# DendroSchem.net
KiCad netlist of a schematic drawn in EAGLE
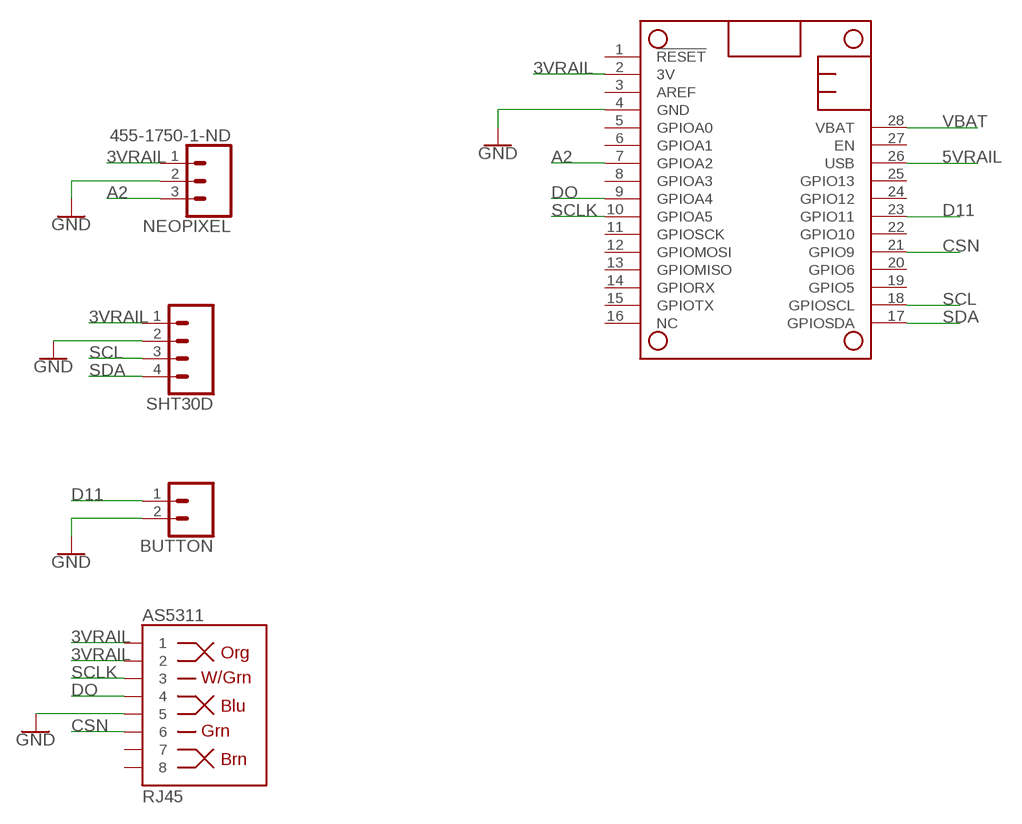
[diagram p0: schematic, sheet 1]

(export (version "E")
  (design (tool "Eeschema 10.0.6"))
  (components
    (comp (ref "AS5311")
      (value "RJ45")
      (footprint "eagle-import:RJ45-8")
      (libsource (lib "eagle-import") (part "RJ45-8"))
    )
    (comp (ref "BUTTON")
      (value "CONN_02")
      (footprint "eagle-import:1X02")
      (libsource (lib "eagle-import") (part "CONN_02"))
    )
    (comp (ref "MS1")
      (value "FEATHERWING")
      (footprint "eagle-import:FEATHERWING")
      (libsource (lib "eagle-import") (part "FEATHERWING"))
    )
    (comp (ref "NEOPIXEL")
      (value "455-1750-1-ND")
      (footprint "eagle-import:1X03")
      (libsource (lib "eagle-import") (part "CONN_03"))
    )
    (comp (ref "SHT30D")
      (value "CONN_04")
      (footprint "eagle-import:1X04")
      (libsource (lib "eagle-import") (part "CONN_04"))
    )
  )
  (nets
    (net (code "1") (name "/3VRAIL") (class "Default")
      (node (ref "AS5311") (pin "1") (pinfunction "1_1") (pintype "bidirectional"))
      (node (ref "AS5311") (pin "2") (pinfunction "2_2") (pintype "bidirectional"))
      (node (ref "MS1") (pin "2") (pinfunction "3V_2") (pintype "power_in"))
      (node (ref "NEOPIXEL") (pin "1") (pinfunction "1_1") (pintype "passive"))
      (node (ref "SHT30D") (pin "1") (pinfunction "1_1") (pintype "passive"))
    )
    (net (code "2") (name "/5VRAIL") (class "Default")
      (node (ref "MS1") (pin "26") (pinfunction "USB_26") (pintype "power_in"))
    )
    (net (code "3") (name "/A2") (class "Default")
      (node (ref "MS1") (pin "7") (pinfunction "GPIOA2_7") (pintype "bidirectional"))
      (node (ref "NEOPIXEL") (pin "3") (pinfunction "3_3") (pintype "passive"))
    )
    (net (code "4") (name "/CSN") (class "Default")
      (node (ref "AS5311") (pin "6") (pinfunction "6_6") (pintype "bidirectional"))
      (node (ref "MS1") (pin "21") (pinfunction "GPIO9_21") (pintype "bidirectional"))
    )
    (net (code "5") (name "/D11") (class "Default")
      (node (ref "BUTTON") (pin "1") (pinfunction "1_1") (pintype "passive"))
      (node (ref "MS1") (pin "23") (pinfunction "GPIO11_23") (pintype "bidirectional"))
    )
    (net (code "6") (name "/DO") (class "Default")
      (node (ref "AS5311") (pin "4") (pinfunction "4_4") (pintype "bidirectional"))
      (node (ref "MS1") (pin "9") (pinfunction "GPIOA4_9") (pintype "bidirectional"))
    )
    (net (code "7") (name "/SCL") (class "Default")
      (node (ref "MS1") (pin "18") (pinfunction "GPIOSCL_18") (pintype "bidirectional"))
      (node (ref "SHT30D") (pin "3") (pinfunction "3_3") (pintype "passive"))
    )
    (net (code "8") (name "/SCLK") (class "Default")
      (node (ref "AS5311") (pin "3") (pinfunction "3_3") (pintype "bidirectional"))
      (node (ref "MS1") (pin "10") (pinfunction "GPIOA5_10") (pintype "bidirectional"))
    )
    (net (code "9") (name "/SDA") (class "Default")
      (node (ref "MS1") (pin "17") (pinfunction "GPIOSDA_17") (pintype "bidirectional"))
      (node (ref "SHT30D") (pin "4") (pinfunction "4_4") (pintype "passive"))
    )
    (net (code "10") (name "/VBAT") (class "Default")
      (node (ref "MS1") (pin "28") (pinfunction "VBAT_28") (pintype "power_in"))
    )
    (net (code "11") (name "GND") (class "Default")
      (node (ref "AS5311") (pin "5") (pinfunction "5_5") (pintype "bidirectional"))
      (node (ref "BUTTON") (pin "2") (pinfunction "2_2") (pintype "passive"))
      (node (ref "MS1") (pin "4") (pinfunction "GND_4") (pintype "power_in"))
      (node (ref "NEOPIXEL") (pin "2") (pinfunction "2_2") (pintype "passive"))
      (node (ref "SHT30D") (pin "2") (pinfunction "2_2") (pintype "passive"))
    )
    (net (code "12") (name "unconnected-(AS5311-Pad7)") (class "Default")
      (node (ref "AS5311") (pin "7") (pinfunction "7_7") (pintype "bidirectional"))
    )
    (net (code "13") (name "unconnected-(AS5311-Pad8)") (class "Default")
      (node (ref "AS5311") (pin "8") (pinfunction "8_8") (pintype "bidirectional"))
    )
    (net (code "14") (name "unconnected-(MS1-AREF-Pad3)") (class "Default")
      (node (ref "MS1") (pin "3") (pinfunction "AREF_3") (pintype "passive"))
    )
    (net (code "15") (name "unconnected-(MS1-EN-Pad27)") (class "Default")
      (node (ref "MS1") (pin "27") (pinfunction "EN_27") (pintype "passive"))
    )
    (net (code "16") (name "unconnected-(MS1-GPIO5-Pad19)") (class "Default")
      (node (ref "MS1") (pin "19") (pinfunction "GPIO5_19") (pintype "bidirectional"))
    )
    (net (code "17") (name "unconnected-(MS1-GPIO6-Pad20)") (class "Default")
      (node (ref "MS1") (pin "20") (pinfunction "GPIO6_20") (pintype "bidirectional"))
    )
    (net (code "18") (name "unconnected-(MS1-GPIO10-Pad22)") (class "Default")
      (node (ref "MS1") (pin "22") (pinfunction "GPIO10_22") (pintype "bidirectional"))
    )
    (net (code "19") (name "unconnected-(MS1-GPIO12-Pad24)") (class "Default")
      (node (ref "MS1") (pin "24") (pinfunction "GPIO12_24") (pintype "bidirectional"))
    )
    (net (code "20") (name "unconnected-(MS1-GPIO13-Pad25)") (class "Default")
      (node (ref "MS1") (pin "25") (pinfunction "GPIO13_25") (pintype "bidirectional"))
    )
    (net (code "21") (name "unconnected-(MS1-GPIOA0-Pad5)") (class "Default")
      (node (ref "MS1") (pin "5") (pinfunction "GPIOA0_5") (pintype "bidirectional"))
    )
    (net (code "22") (name "unconnected-(MS1-GPIOA1-Pad6)") (class "Default")
      (node (ref "MS1") (pin "6") (pinfunction "GPIOA1_6") (pintype "bidirectional"))
    )
    (net (code "23") (name "unconnected-(MS1-GPIOA3-Pad8)") (class "Default")
      (node (ref "MS1") (pin "8") (pinfunction "GPIOA3_8") (pintype "bidirectional"))
    )
    (net (code "24") (name "unconnected-(MS1-GPIOMISO-Pad13)") (class "Default")
      (node (ref "MS1") (pin "13") (pinfunction "GPIOMISO_13") (pintype "bidirectional"))
    )
    (net (code "25") (name "unconnected-(MS1-GPIOMOSI-Pad12)") (class "Default")
      (node (ref "MS1") (pin "12") (pinfunction "GPIOMOSI_12") (pintype "bidirectional"))
    )
    (net (code "26") (name "unconnected-(MS1-GPIORX-Pad14)") (class "Default")
      (node (ref "MS1") (pin "14") (pinfunction "GPIORX_14") (pintype "bidirectional"))
    )
    (net (code "27") (name "unconnected-(MS1-GPIOSCK-Pad11)") (class "Default")
      (node (ref "MS1") (pin "11") (pinfunction "GPIOSCK_11") (pintype "bidirectional"))
    )
    (net (code "28") (name "unconnected-(MS1-GPIOTX-Pad15)") (class "Default")
      (node (ref "MS1") (pin "15") (pinfunction "GPIOTX_15") (pintype "bidirectional"))
    )
    (net (code "29") (name "unconnected-(MS1-NC-Pad16)") (class "Default")
      (node (ref "MS1") (pin "16") (pinfunction "NC_16") (pintype "passive"))
    )
    (net (code "30") (name "unconnected-(MS1-~{RESET}-Pad1)") (class "Default")
      (node (ref "MS1") (pin "1") (pinfunction "~{RESET}_1") (pintype "input"))
    )
  )
)
